# lm3410-boost-flashlight-driver-17mm-mk-1.net
KiCad netlist of a schematic drawn in EAGLE
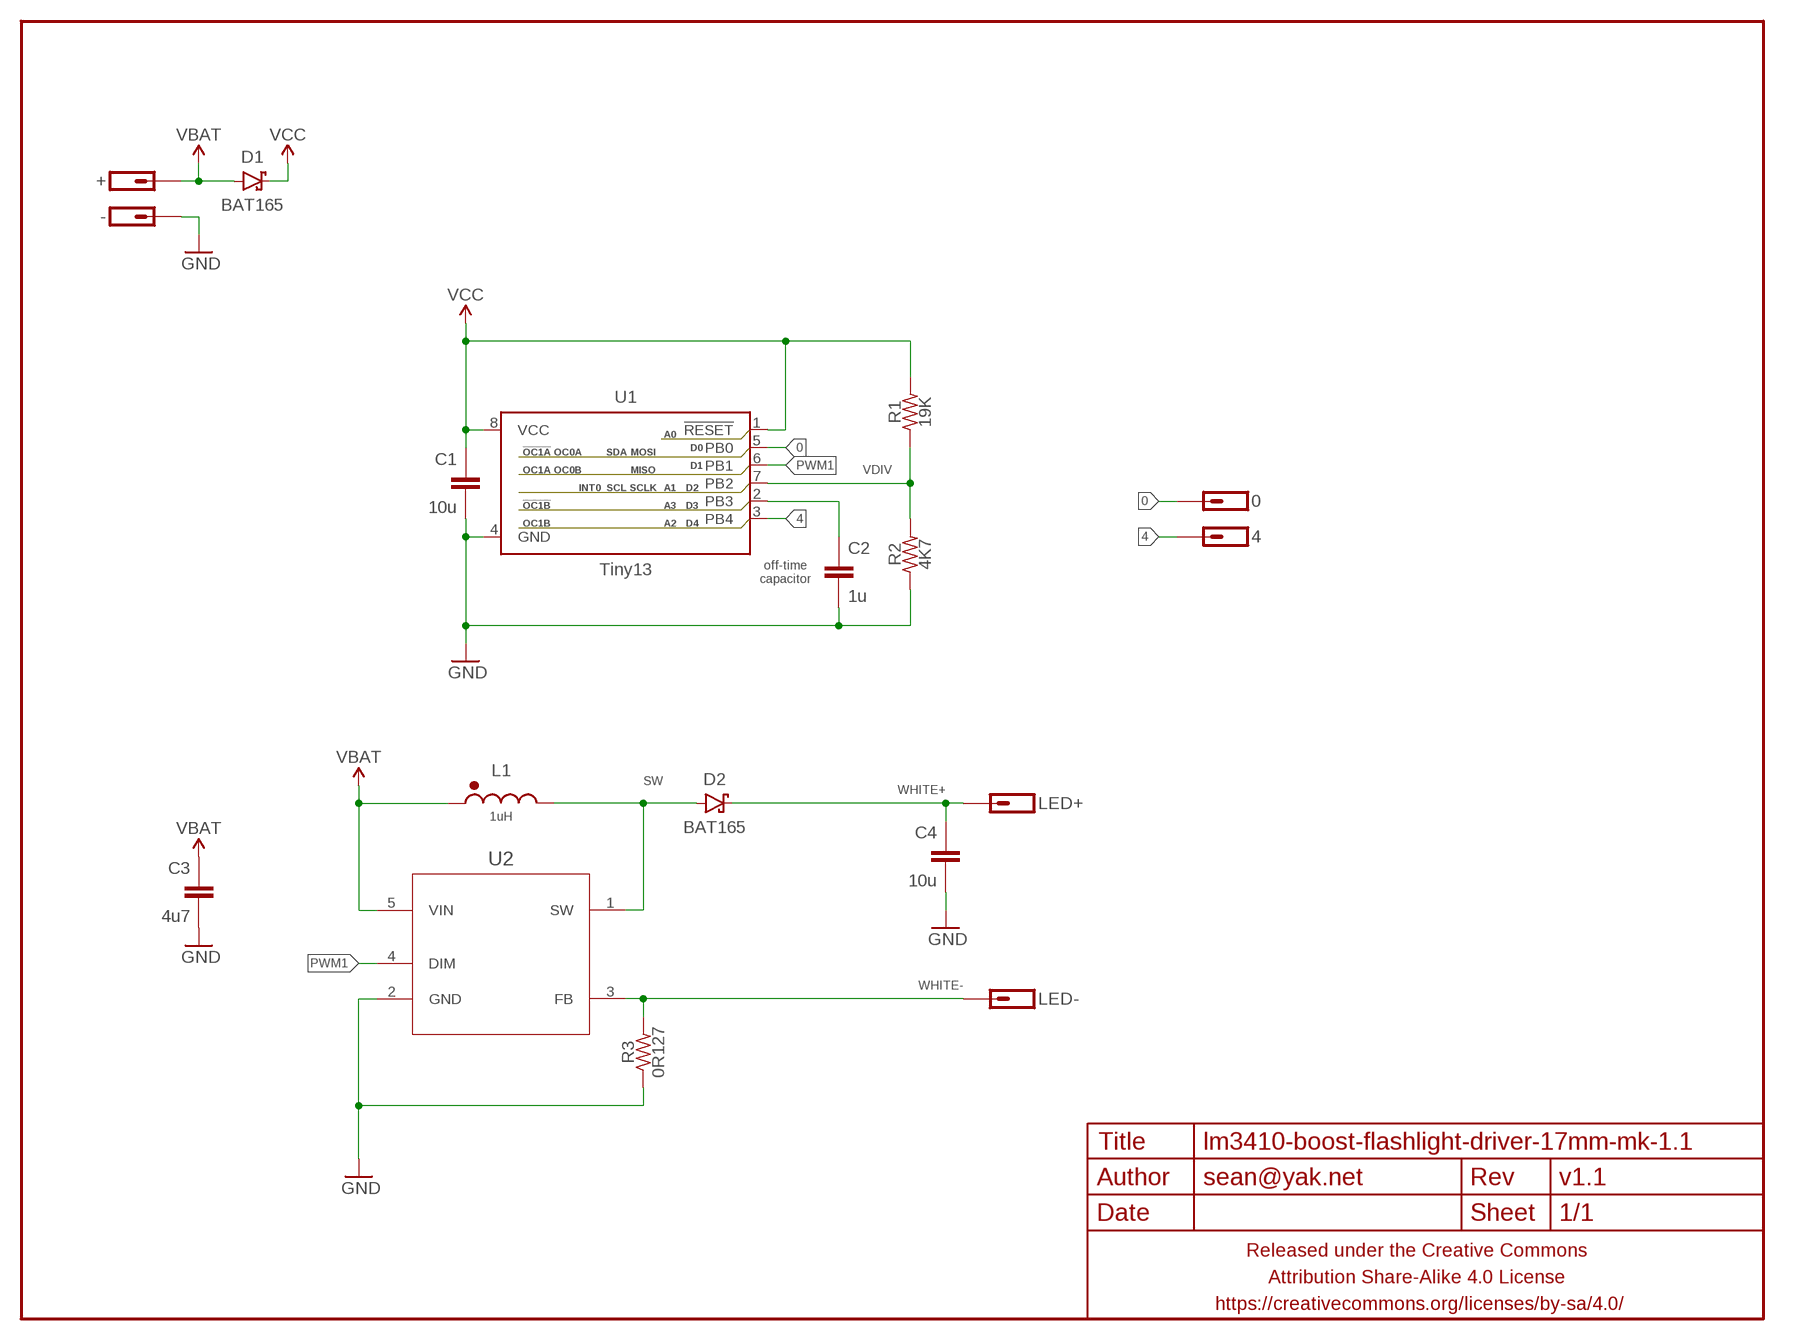
[diagram p0: schematic, sheet 1]

(export (version "E")
  (design (tool "Eeschema 10.0.6"))
  (components
    (comp (ref "+")
      (value "M01PTH-1MM-CIR-NS")
      (footprint "eagle-import:1X01-1MM-CIR-NS")
      (libsource (lib "eagle-import") (part "M01PTH-1MM-CIR-NS"))
    )
    (comp (ref "-")
      (value "M01NOT-A-VIA-NOPE")
      (footprint "eagle-import:1X01_NOSILK_NOSTOP")
      (libsource (lib "eagle-import") (part "M01NOT-A-VIA-NOPE"))
    )
    (comp (ref "0")
      (value "M01SMD-1MM-DIA-NS")
      (footprint "eagle-import:1X01-SMD-1MM-DIA-NS")
      (libsource (lib "eagle-import") (part "M01SMD-1MM-DIA-NS"))
    )
    (comp (ref "4")
      (value "M01SMD-1MM-DIA-NS")
      (footprint "eagle-import:1X01-SMD-1MM-DIA-NS")
      (libsource (lib "eagle-import") (part "M01SMD-1MM-DIA-NS"))
    )
    (comp (ref "C1")
      (value "10u")
      (footprint "eagle-import:C0603-TIGHTER")
      (libsource (lib "eagle-import") (part "CAPACITOR-CERAMICC0603-TIGHTER"))
    )
    (comp (ref "C2")
      (value "1u")
      (footprint "eagle-import:C0603-TIGHTER")
      (libsource (lib "eagle-import") (part "CAPACITOR-CERAMICC0603-TIGHTER"))
    )
    (comp (ref "C3")
      (value "4u7")
      (footprint "eagle-import:C0603-TIGHTER")
      (libsource (lib "eagle-import") (part "CAPACITOR-CERAMICC0603-TIGHTER"))
    )
    (comp (ref "C4")
      (value "10u")
      (footprint "eagle-import:C0603-TIGHTER")
      (libsource (lib "eagle-import") (part "CAPACITOR-CERAMICC0603-TIGHTER"))
    )
    (comp (ref "D1")
      (value "BAT165")
      (footprint "eagle-import:SOD323-SCHOTTKY")
      (libsource (lib "eagle-import") (part "DIODE-SCHOTTKYSOD323"))
    )
    (comp (ref "D2")
      (value "BAT165")
      (footprint "eagle-import:SOD323-SCHOTTKY")
      (libsource (lib "eagle-import") (part "DIODE-SCHOTTKYSOD323"))
    )
    (comp (ref "FRAME1")
      (value "FRAME-LETTERNO_PACKAGE")
      (footprint "eagle-import:DUMMY")
      (fields (field (name "DESIGNER") "sean@yak.net") (field (name "VERSION") "v1.1"))
      (libsource (lib "eagle-import") (part "FRAME-LETTERNO_PACKAGE"))
    )
    (comp (ref "L1")
      (value "1uH")
      (footprint "eagle-import:PFL2512")
      (libsource (lib "eagle-import") (part "INDUCTORPFL2512"))
    )
    (comp (ref "LED+")
      (value "M01PTH-1.2MM-NS")
      (footprint "eagle-import:1X01-1.2MM-NS")
      (libsource (lib "eagle-import") (part "M01PTH-1.2MM-NS"))
    )
    (comp (ref "LED-")
      (value "M01PTH-1.2MM-NS")
      (footprint "eagle-import:1X01-1.2MM-NS")
      (libsource (lib "eagle-import") (part "M01PTH-1.2MM-NS"))
    )
    (comp (ref "R1")
      (value "19K")
      (footprint "eagle-import:R0603-TIGHTER")
      (libsource (lib "eagle-import") (part "RESISTORR0603-TIGHTER"))
    )
    (comp (ref "R2")
      (value "4K7")
      (footprint "eagle-import:R0603-TIGHTER")
      (libsource (lib "eagle-import") (part "RESISTORR0603-TIGHTER"))
    )
    (comp (ref "R3")
      (value "0R127")
      (footprint "eagle-import:R0805")
      (libsource (lib "eagle-import") (part "RESISTORR0805"))
    )
    (comp (ref "U1")
      (value "Tiny13")
      (footprint "eagle-import:SO08-NARROWER")
      (libsource (lib "eagle-import") (part "ATTINY13SOIC-NARROWPADS"))
    )
    (comp (ref "U2")
      (value "LM3410XMF")
      (footprint "eagle-import:SOT95P285X120-5N")
      (libsource (lib "eagle-import") (part "LM3410XMF"))
    )
  )
  (nets
    (net (code "1") (name "/SW") (class "Default")
      (node (ref "D2") (pin "A") (pinfunction "A_A") (pintype "passive"))
      (node (ref "L1") (pin "P$2") (pinfunction "2_P$2") (pintype "passive"))
      (node (ref "U2") (pin "1") (pinfunction "SW_1") (pintype "output"))
    )
    (net (code "2") (name "/VDIV") (class "Default")
      (node (ref "R1") (pin "1") (pinfunction "1_1") (pintype "passive"))
      (node (ref "R2") (pin "2") (pinfunction "2_2") (pintype "passive"))
      (node (ref "U1") (pin "7") (pinfunction "PB2_7") (pintype "bidirectional"))
    )
    (net (code "3") (name "/WHITE+") (class "Default")
      (node (ref "C4") (pin "1") (pinfunction "1_1") (pintype "passive"))
      (node (ref "D2") (pin "C") (pinfunction "C_C") (pintype "passive"))
      (node (ref "LED+") (pin "P$1") (pinfunction "1_P$1") (pintype "passive"))
    )
    (net (code "4") (name "/WHITE-") (class "Default")
      (node (ref "LED-") (pin "P$1") (pinfunction "1_P$1") (pintype "passive"))
      (node (ref "R3") (pin "2") (pinfunction "2_2") (pintype "passive"))
      (node (ref "U2") (pin "3") (pinfunction "FB_3") (pintype "input"))
    )
    (net (code "5") (name "0") (class "Default")
      (node (ref "0") (pin "P$1") (pinfunction "1_P$1") (pintype "passive"))
      (node (ref "U1") (pin "5") (pinfunction "PB0_5") (pintype "bidirectional"))
    )
    (net (code "6") (name "4") (class "Default")
      (node (ref "4") (pin "P$1") (pinfunction "1_P$1") (pintype "passive"))
      (node (ref "U1") (pin "3") (pinfunction "PB4_3") (pintype "bidirectional"))
    )
    (net (code "7") (name "GND") (class "Default")
      (node (ref "-") (pin "P$1") (pinfunction "1_P$1") (pintype "passive"))
      (node (ref "C1") (pin "2") (pinfunction "2_2") (pintype "passive"))
      (node (ref "C2") (pin "2") (pinfunction "2_2") (pintype "passive"))
      (node (ref "C3") (pin "2") (pinfunction "2_2") (pintype "passive"))
      (node (ref "C4") (pin "2") (pinfunction "2_2") (pintype "passive"))
      (node (ref "R2") (pin "1") (pinfunction "1_1") (pintype "passive"))
      (node (ref "R3") (pin "1") (pinfunction "1_1") (pintype "passive"))
      (node (ref "U1") (pin "4") (pinfunction "GND_4") (pintype "bidirectional"))
      (node (ref "U2") (pin "2") (pinfunction "GND_2") (pintype "passive"))
    )
    (net (code "8") (name "Net-(U1-PB3)") (class "Default")
      (node (ref "C2") (pin "1") (pinfunction "1_1") (pintype "passive"))
      (node (ref "U1") (pin "2") (pinfunction "PB3_2") (pintype "bidirectional"))
    )
    (net (code "9") (name "PWM1") (class "Default")
      (node (ref "U1") (pin "6") (pinfunction "PB1_6") (pintype "bidirectional"))
      (node (ref "U2") (pin "4") (pinfunction "DIM_4") (pintype "input"))
    )
    (net (code "10") (name "VBAT") (class "Default")
      (node (ref "+") (pin "1") (pinfunction "1_1") (pintype "passive"))
      (node (ref "C3") (pin "1") (pinfunction "1_1") (pintype "passive"))
      (node (ref "D1") (pin "A") (pinfunction "A_A") (pintype "passive"))
      (node (ref "L1") (pin "P$1") (pinfunction "1_P$1") (pintype "passive"))
      (node (ref "U2") (pin "5") (pinfunction "VIN_5") (pintype "power_in"))
    )
    (net (code "11") (name "VCC") (class "Default")
      (node (ref "C1") (pin "1") (pinfunction "1_1") (pintype "passive"))
      (node (ref "D1") (pin "C") (pinfunction "C_C") (pintype "passive"))
      (node (ref "R1") (pin "2") (pinfunction "2_2") (pintype "passive"))
      (node (ref "U1") (pin "1") (pinfunction "~{RESET}_1") (pintype "bidirectional"))
      (node (ref "U1") (pin "8") (pinfunction "VCC_8") (pintype "bidirectional"))
    )
  )
)
